# SubHarmonics_Main_Board_v2.net
KiCad netlist of a schematic drawn in EAGLE
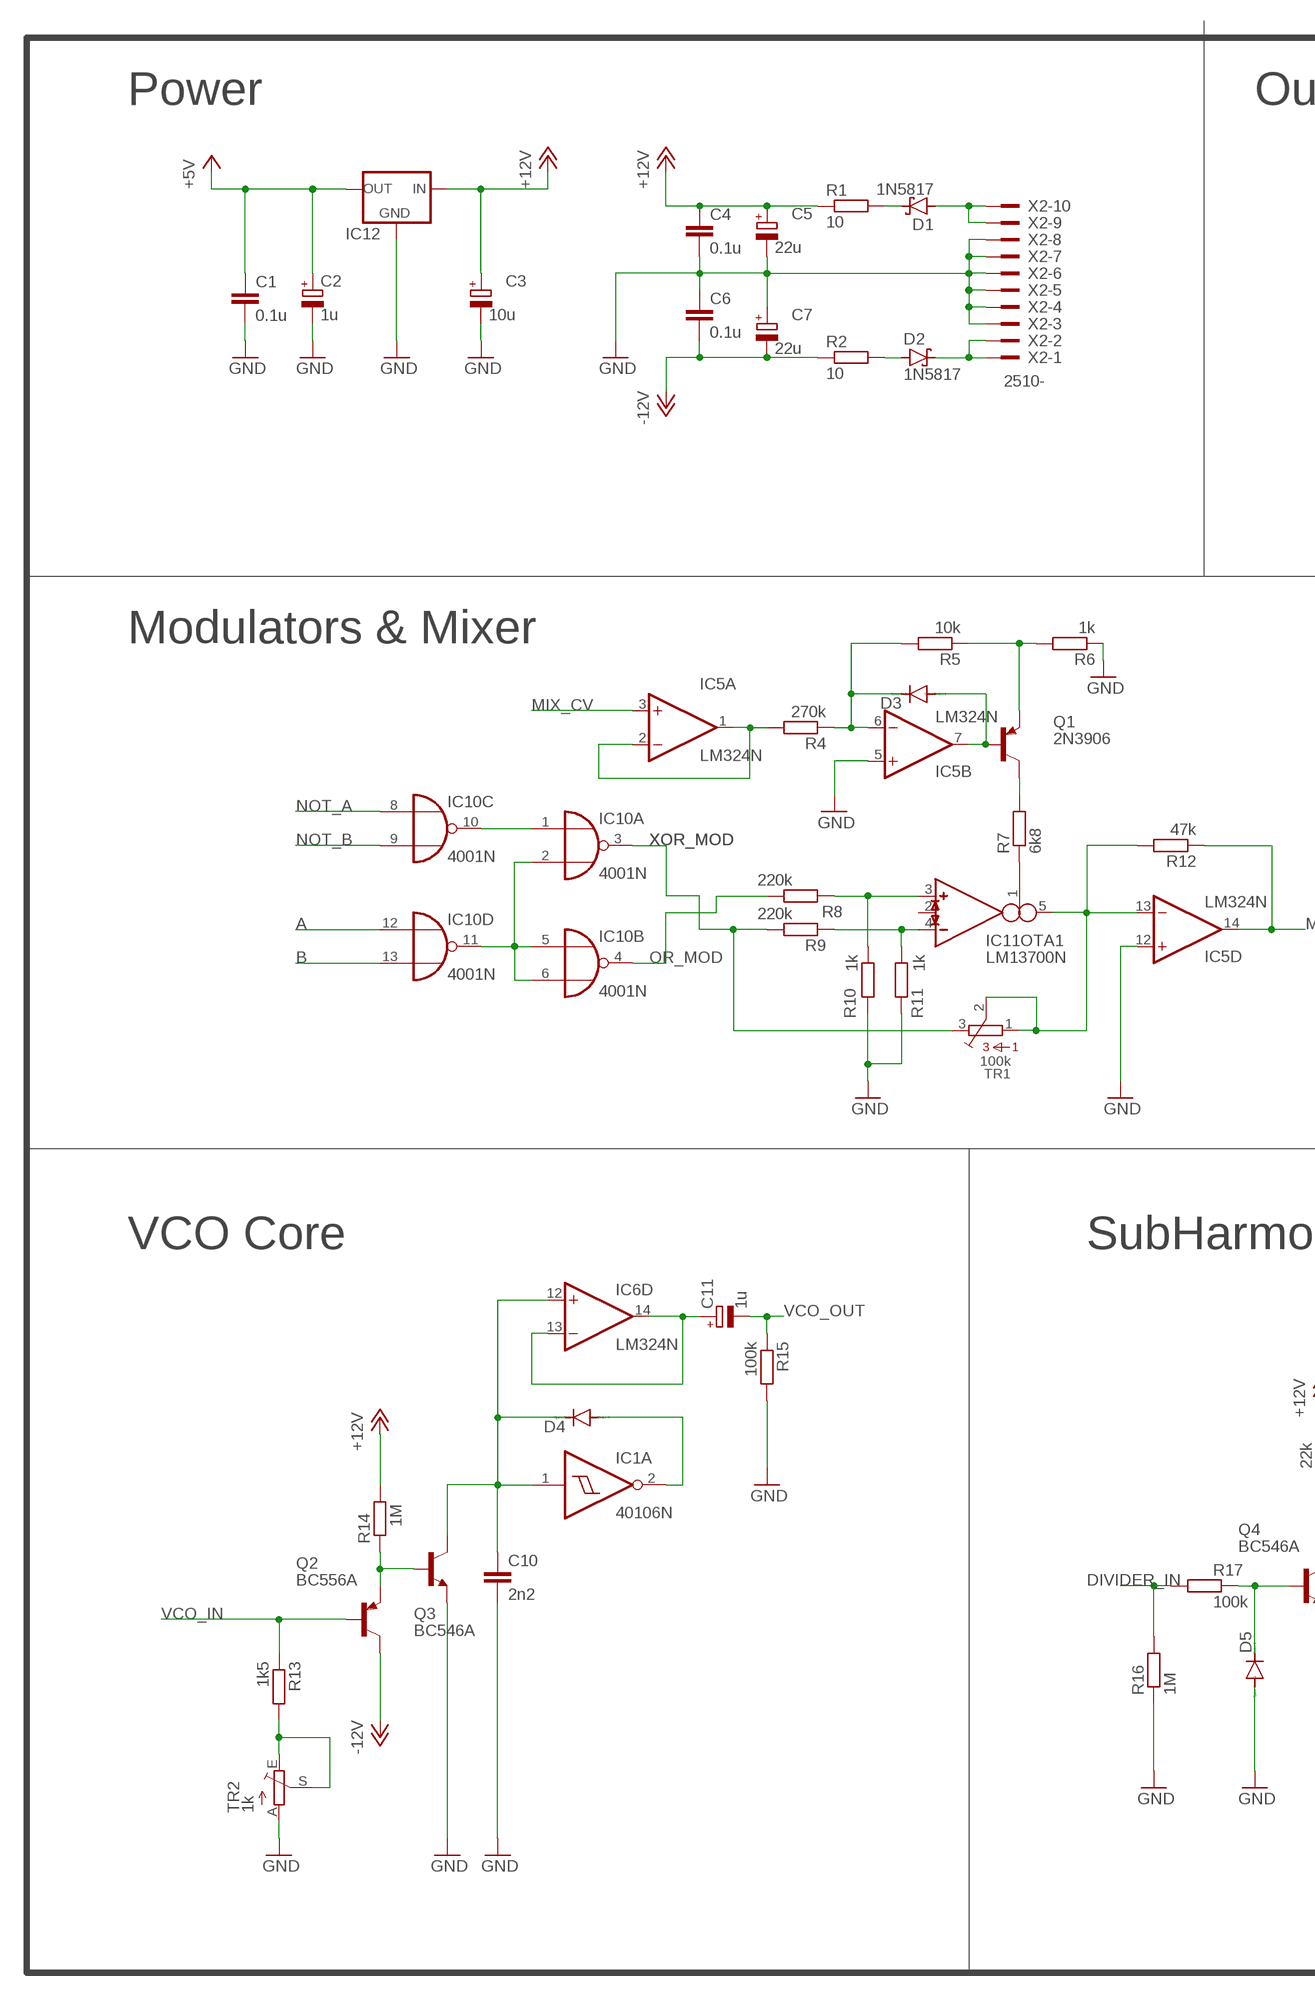
[diagram p0: schematic, sheet 1, part 1 of 2]
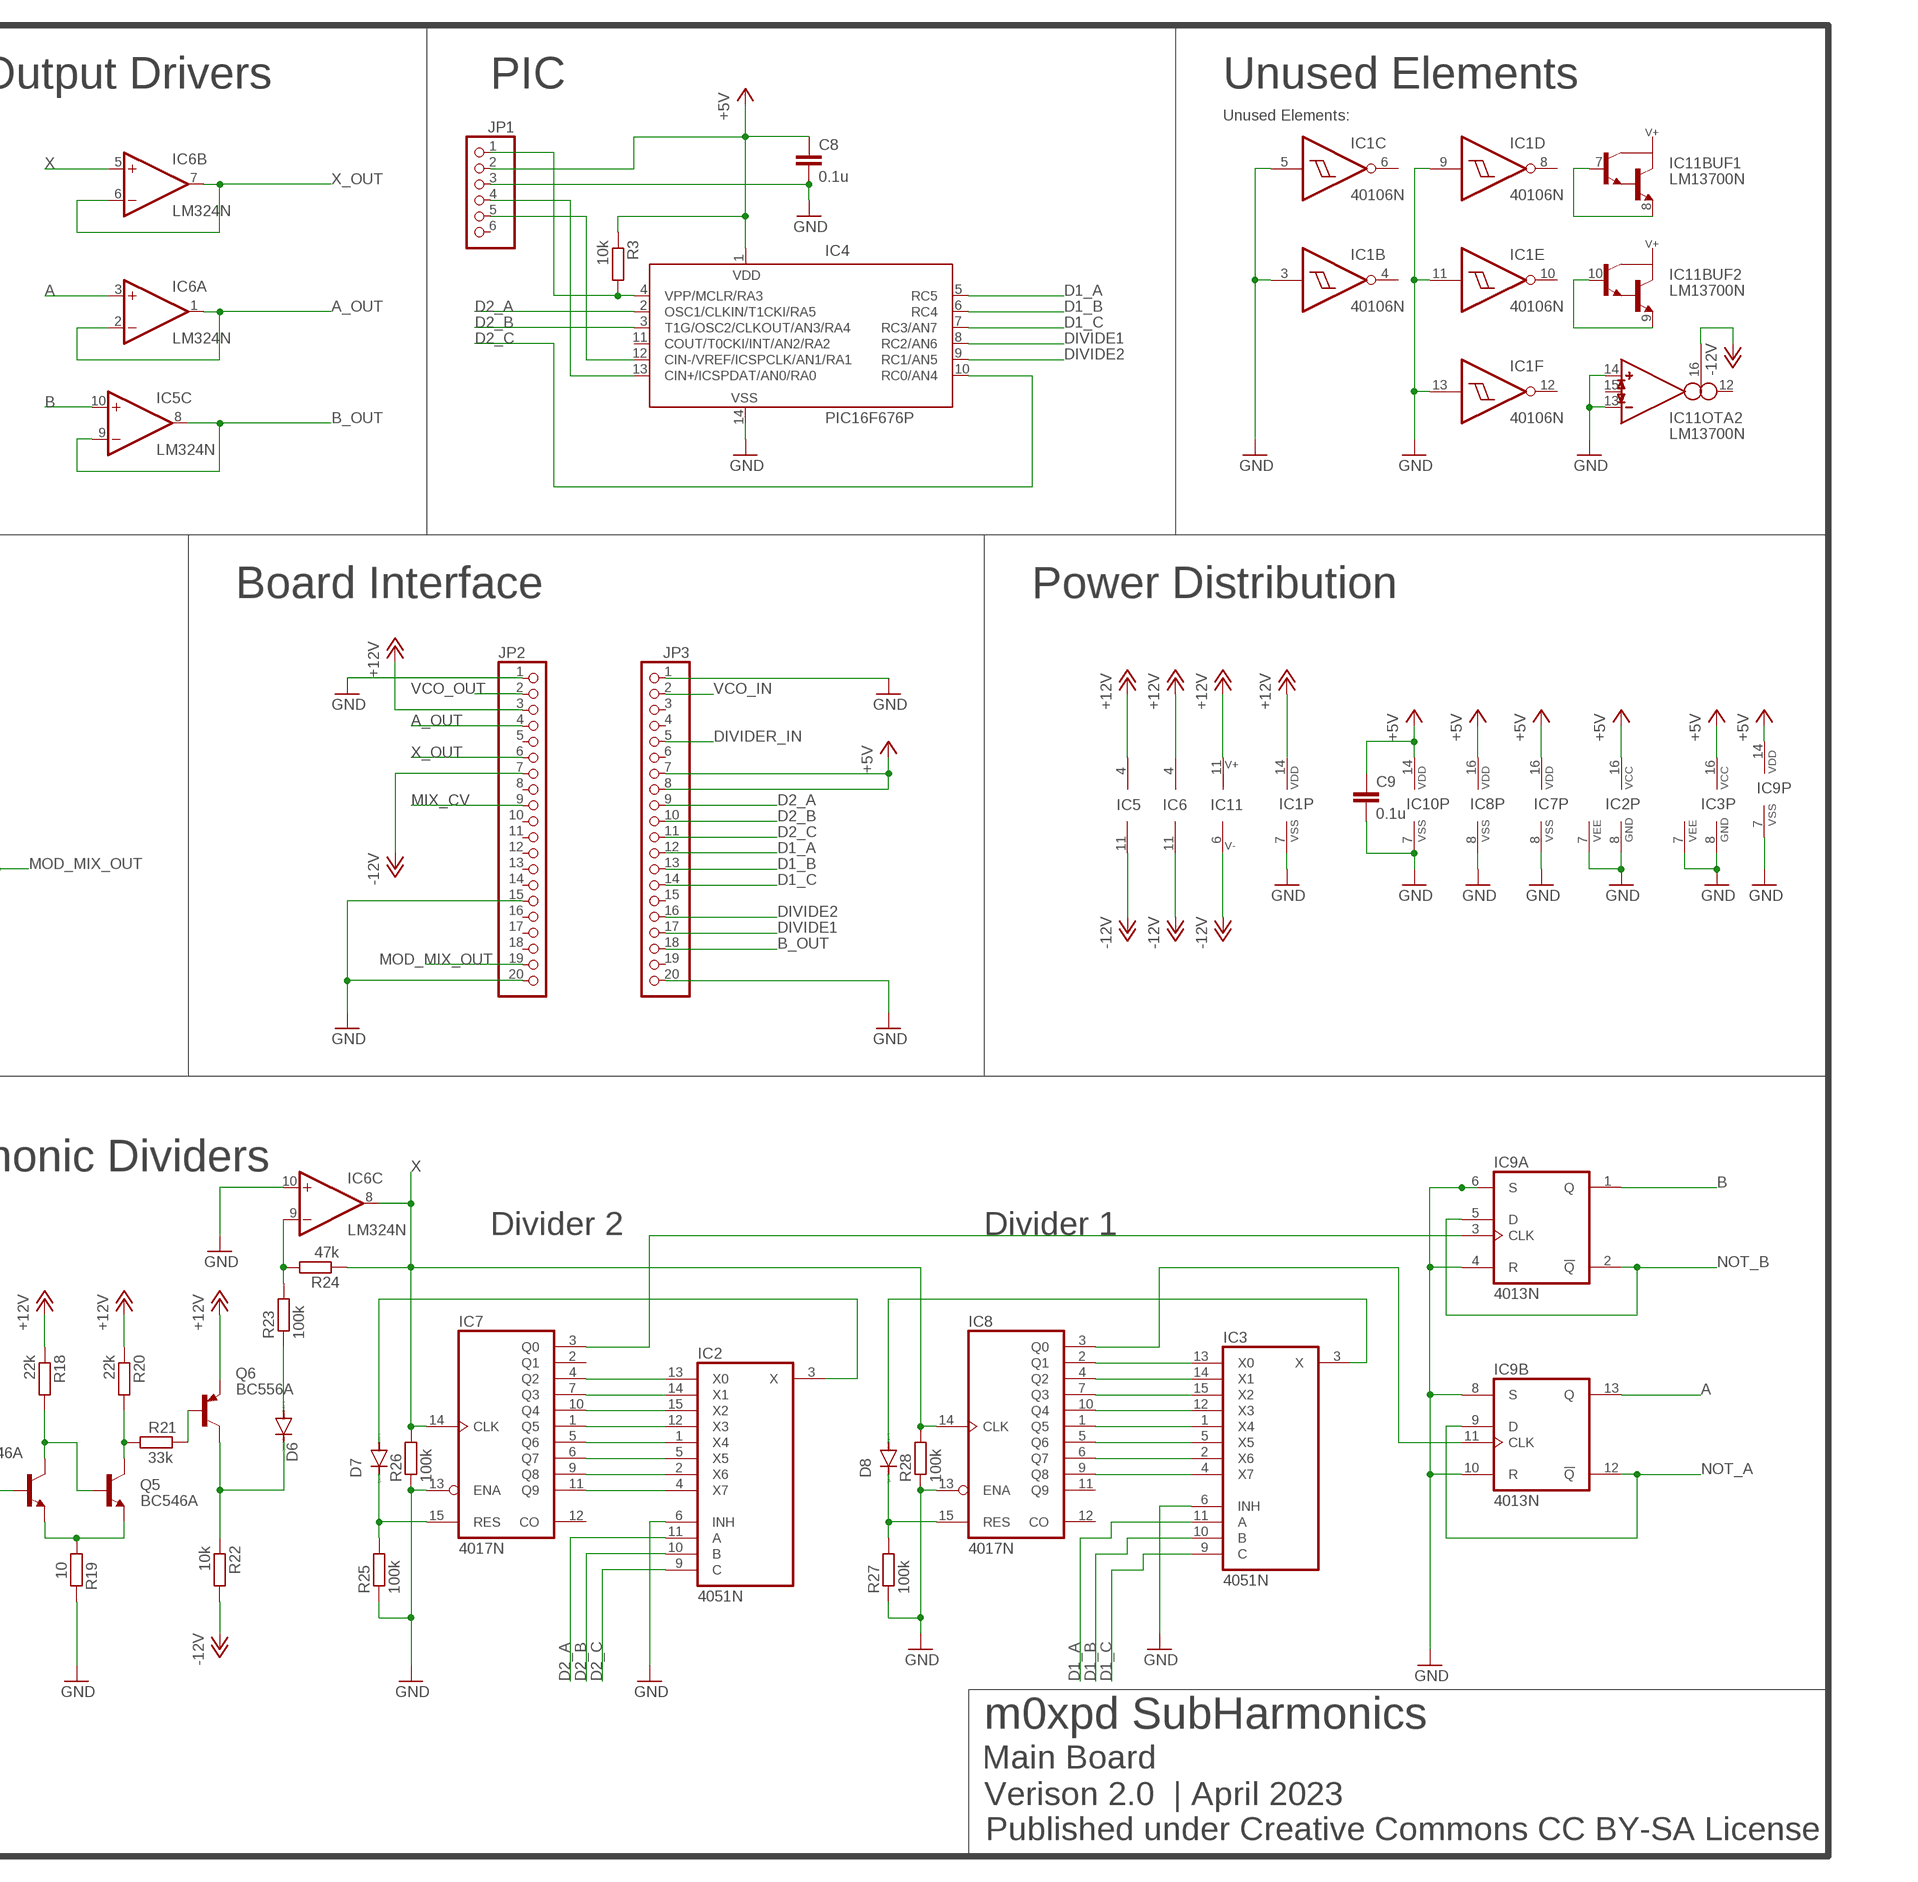
[diagram p1: schematic, sheet 1, part 2 of 2]

(export (version "E")
  (design (tool "Eeschema 10.0.6"))
  (components
    (comp (ref "C1")
      (value "0.1u")
      (footprint "eagle-import:C050-025X075")
      (libsource (lib "eagle-import") (part "C-EU050-025X075"))
    )
    (comp (ref "C2")
      (value "1u")
      (footprint "eagle-import:E2,5-5")
      (libsource (lib "eagle-import") (part "CPOL-EUE2.5-5"))
    )
    (comp (ref "C3")
      (value "10u")
      (footprint "eagle-import:E2,5-5")
      (libsource (lib "eagle-import") (part "CPOL-EUE2.5-5"))
    )
    (comp (ref "C4")
      (value "0.1u")
      (footprint "eagle-import:C050-025X075")
      (libsource (lib "eagle-import") (part "C-EU050-025X075"))
    )
    (comp (ref "C5")
      (value "22u")
      (footprint "eagle-import:E2,5-5")
      (libsource (lib "eagle-import") (part "CPOL-EUE2.5-5"))
    )
    (comp (ref "C6")
      (value "0.1u")
      (footprint "eagle-import:C050-025X075")
      (libsource (lib "eagle-import") (part "C-EU050-025X075"))
    )
    (comp (ref "C7")
      (value "22u")
      (footprint "eagle-import:E2,5-5")
      (libsource (lib "eagle-import") (part "CPOL-EUE2.5-5"))
    )
    (comp (ref "C8")
      (value "0.1u")
      (footprint "eagle-import:C050-025X075")
      (libsource (lib "eagle-import") (part "C-EU050-025X075"))
    )
    (comp (ref "C9")
      (value "0.1u")
      (footprint "eagle-import:C050-025X075")
      (libsource (lib "eagle-import") (part "C-EU050-025X075"))
    )
    (comp (ref "C10")
      (value "2n2")
      (footprint "eagle-import:C050-030X075")
      (libsource (lib "eagle-import") (part "C-EU050-030X075"))
    )
    (comp (ref "C11")
      (value "1u")
      (footprint "eagle-import:E2,5-5")
      (libsource (lib "eagle-import") (part "CPOL-EUE2.5-5"))
    )
    (comp (ref "D1")
      (value "1N5817")
      (footprint "eagle-import:DO35-7")
      (libsource (lib "eagle-import") (part "SCHOTTKY-DIODEDO35-7"))
    )
    (comp (ref "D2")
      (value "1N5817")
      (footprint "eagle-import:DO35-7")
      (libsource (lib "eagle-import") (part "SCHOTTKY-DIODEDO35-7"))
    )
    (comp (ref "D3")
      (value "1N4148DO35-7")
      (footprint "eagle-import:DO35-7")
      (libsource (lib "eagle-import") (part "1N4148DO35-7"))
    )
    (comp (ref "D4")
      (value "1N4148DO35-7")
      (footprint "eagle-import:DO35-7")
      (libsource (lib "eagle-import") (part "1N4148DO35-7"))
    )
    (comp (ref "D5")
      (value "1N4148DO35-7")
      (footprint "eagle-import:DO35-7")
      (libsource (lib "eagle-import") (part "1N4148DO35-7"))
    )
    (comp (ref "D6")
      (value "1N4148DO35-7")
      (footprint "eagle-import:DO35-7")
      (libsource (lib "eagle-import") (part "1N4148DO35-7"))
    )
    (comp (ref "D7")
      (value "1N4148DO35-7")
      (footprint "eagle-import:DO35-7")
      (libsource (lib "eagle-import") (part "1N4148DO35-7"))
    )
    (comp (ref "D8")
      (value "1N4148DO35-7")
      (footprint "eagle-import:DO35-7")
      (libsource (lib "eagle-import") (part "1N4148DO35-7"))
    )
    (comp (ref "IC1")
      (value "40106N")
      (footprint "eagle-import:DIL14")
      (libsource (lib "eagle-import") (part "40106N"))
    )
    (comp (ref "IC2")
      (value "4051N")
      (footprint "eagle-import:DIL16")
      (libsource (lib "eagle-import") (part "4051N"))
    )
    (comp (ref "IC3")
      (value "4051N")
      (footprint "eagle-import:DIL16")
      (libsource (lib "eagle-import") (part "4051N"))
    )
    (comp (ref "IC4")
      (value "PIC16F676P")
      (footprint "eagle-import:DIL14")
      (fields (field (name "MF") "MICROCHIP") (field (name "MPN") "PIC16F676-I/P"))
      (libsource (lib "eagle-import") (part "PIC16F676P"))
    )
    (comp (ref "IC5")
      (value "LM324N")
      (footprint "eagle-import:DIL14")
      (libsource (lib "eagle-import") (part "LM324N"))
    )
    (comp (ref "IC6")
      (value "LM324N")
      (footprint "eagle-import:DIL14")
      (libsource (lib "eagle-import") (part "LM324N"))
    )
    (comp (ref "IC7")
      (value "4017N")
      (footprint "eagle-import:DIL16")
      (libsource (lib "eagle-import") (part "4017N"))
    )
    (comp (ref "IC8")
      (value "4017N")
      (footprint "eagle-import:DIL16")
      (libsource (lib "eagle-import") (part "4017N"))
    )
    (comp (ref "IC9")
      (value "4013N")
      (footprint "eagle-import:DIL14")
      (libsource (lib "eagle-import") (part "4013N"))
    )
    (comp (ref "IC10")
      (value "4001N")
      (footprint "eagle-import:DIL14")
      (libsource (lib "eagle-import") (part "4001N"))
    )
    (comp (ref "IC11")
      (value "LM13700N")
      (footprint "eagle-import:DIL16")
      (libsource (lib "eagle-import") (part "LM13700N"))
    )
    (comp (ref "IC12")
      (value "78LXX")
      (footprint "eagle-import:78LXX")
      (libsource (lib "eagle-import") (part "78LXX"))
    )
    (comp (ref "JP1")
      (value "PINHD-1X6")
      (footprint "eagle-import:1X06")
      (libsource (lib "eagle-import") (part "PINHD-1X6"))
    )
    (comp (ref "JP2")
      (value "PINHD-1X20")
      (footprint "eagle-import:1X20")
      (libsource (lib "eagle-import") (part "PINHD-1X20"))
    )
    (comp (ref "JP3")
      (value "PINHD-1X20")
      (footprint "eagle-import:1X20")
      (libsource (lib "eagle-import") (part "PINHD-1X20"))
    )
    (comp (ref "Q1")
      (value "2N3906")
      (footprint "eagle-import:TO92")
      (libsource (lib "eagle-import") (part "2N3906"))
    )
    (comp (ref "Q2")
      (value "BC556A")
      (footprint "eagle-import:TO92-EBC")
      (libsource (lib "eagle-import") (part "BC556A"))
    )
    (comp (ref "Q3")
      (value "BC546A")
      (footprint "eagle-import:TO92-EBC")
      (libsource (lib "eagle-import") (part "BC546A"))
    )
    (comp (ref "Q4")
      (value "BC546A")
      (footprint "eagle-import:TO92-EBC")
      (libsource (lib "eagle-import") (part "BC546A"))
    )
    (comp (ref "Q5")
      (value "BC546A")
      (footprint "eagle-import:TO92-EBC")
      (libsource (lib "eagle-import") (part "BC546A"))
    )
    (comp (ref "Q6")
      (value "BC556A")
      (footprint "eagle-import:TO92-EBC")
      (libsource (lib "eagle-import") (part "BC556"))
    )
    (comp (ref "R1")
      (value "10")
      (footprint "eagle-import:0204_7")
      (libsource (lib "eagle-import") (part "R-EU_0204/7"))
    )
    (comp (ref "R2")
      (value "10")
      (footprint "eagle-import:0204_7")
      (libsource (lib "eagle-import") (part "R-EU_0204/7"))
    )
    (comp (ref "R3")
      (value "10k")
      (footprint "eagle-import:0204_7")
      (libsource (lib "eagle-import") (part "R-EU_0204/7"))
    )
    (comp (ref "R4")
      (value "270k")
      (footprint "eagle-import:0204_7")
      (libsource (lib "eagle-import") (part "R-EU_0204/7"))
    )
    (comp (ref "R5")
      (value "10k")
      (footprint "eagle-import:0204_7")
      (libsource (lib "eagle-import") (part "R-EU_0204/7"))
    )
    (comp (ref "R6")
      (value "1k")
      (footprint "eagle-import:0204_7")
      (libsource (lib "eagle-import") (part "R-EU_0204/7"))
    )
    (comp (ref "R7")
      (value "6k8")
      (footprint "eagle-import:0204_7")
      (libsource (lib "eagle-import") (part "R-EU_0204/7"))
    )
    (comp (ref "R8")
      (value "220k")
      (footprint "eagle-import:0204_7")
      (libsource (lib "eagle-import") (part "R-EU_0204/7"))
    )
    (comp (ref "R9")
      (value "220k")
      (footprint "eagle-import:0204_7")
      (libsource (lib "eagle-import") (part "R-EU_0204/7"))
    )
    (comp (ref "R10")
      (value "1k")
      (footprint "eagle-import:0204_7")
      (libsource (lib "eagle-import") (part "R-EU_0204/7"))
    )
    (comp (ref "R11")
      (value "1k")
      (footprint "eagle-import:0204_7")
      (libsource (lib "eagle-import") (part "R-EU_0204/7"))
    )
    (comp (ref "R12")
      (value "47k")
      (footprint "eagle-import:0204_7")
      (libsource (lib "eagle-import") (part "R-EU_0204/7"))
    )
    (comp (ref "R13")
      (value "1k5")
      (footprint "eagle-import:0204_7")
      (libsource (lib "eagle-import") (part "R-EU_0204/7"))
    )
    (comp (ref "R14")
      (value "1M")
      (footprint "eagle-import:0204_7")
      (libsource (lib "eagle-import") (part "R-EU_0204/7"))
    )
    (comp (ref "R15")
      (value "100k")
      (footprint "eagle-import:0204_7")
      (libsource (lib "eagle-import") (part "R-EU_0204/7"))
    )
    (comp (ref "R16")
      (value "1M")
      (footprint "eagle-import:0204_7")
      (libsource (lib "eagle-import") (part "R-EU_0204/7"))
    )
    (comp (ref "R17")
      (value "100k")
      (footprint "eagle-import:0204_7")
      (libsource (lib "eagle-import") (part "R-EU_0204/7"))
    )
    (comp (ref "R18")
      (value "22k")
      (footprint "eagle-import:0204_7")
      (libsource (lib "eagle-import") (part "R-EU_0204/7"))
    )
    (comp (ref "R19")
      (value "10")
      (footprint "eagle-import:0204_7")
      (libsource (lib "eagle-import") (part "R-EU_0204/7"))
    )
    (comp (ref "R20")
      (value "22k")
      (footprint "eagle-import:0204_7")
      (libsource (lib "eagle-import") (part "R-EU_0204/7"))
    )
    (comp (ref "R21")
      (value "33k")
      (footprint "eagle-import:0204_7")
      (libsource (lib "eagle-import") (part "R-EU_0204/7"))
    )
    (comp (ref "R22")
      (value "10k")
      (footprint "eagle-import:0204_7")
      (libsource (lib "eagle-import") (part "R-EU_0204/7"))
    )
    (comp (ref "R23")
      (value "100k")
      (footprint "eagle-import:0204_7")
      (libsource (lib "eagle-import") (part "R-EU_0204/7"))
    )
    (comp (ref "R24")
      (value "47k")
      (footprint "eagle-import:0204_7")
      (libsource (lib "eagle-import") (part "R-EU_0204/7"))
    )
    (comp (ref "R25")
      (value "100k")
      (footprint "eagle-import:0204_7")
      (libsource (lib "eagle-import") (part "R-EU_0204/7"))
    )
    (comp (ref "R26")
      (value "100k")
      (footprint "eagle-import:0204_7")
      (libsource (lib "eagle-import") (part "R-EU_0204/7"))
    )
    (comp (ref "R27")
      (value "100k")
      (footprint "eagle-import:0204_7")
      (libsource (lib "eagle-import") (part "R-EU_0204/7"))
    )
    (comp (ref "R28")
      (value "100k")
      (footprint "eagle-import:0204_7")
      (libsource (lib "eagle-import") (part "R-EU_0204/7"))
    )
    (comp (ref "TR1")
      (value "100k")
      (footprint "eagle-import:BOURNS_3362P_TRIMMER")
      (libsource (lib "eagle-import") (part "BOURNS_3362P_TRIMMERP"))
    )
    (comp (ref "TR2")
      (value "1k")
      (footprint "eagle-import:B64Y")
      (libsource (lib "eagle-import") (part "TRIM_EU-B64Y"))
    )
    (comp (ref "X2")
      (value "2510-")
      (footprint "eagle-import:PAK100_2500-10")
      (fields (field (name "MF") "3M") (field (name "MPN") "2510-6002UB"))
      (libsource (lib "eagle-import") (part "2510-"))
    )
  )
  (nets
    (net (code "1") (name "+5V") (class "Default")
      (node (ref "C1") (pin "1") (pinfunction "1_1") (pintype "passive"))
      (node (ref "C2") (pin "+") (pinfunction "+_+") (pintype "passive"))
      (node (ref "C8") (pin "1") (pinfunction "1_1") (pintype "passive"))
      (node (ref "C9") (pin "1") (pinfunction "1_1") (pintype "passive"))
      (node (ref "IC10") (pin "14") (pinfunction "VDD_14") (pintype "power_in"))
      (node (ref "IC12") (pin "OUT") (pinfunction "OUT_OUT") (pintype "passive"))
      (node (ref "IC2") (pin "16") (pinfunction "VCC_16") (pintype "power_in"))
      (node (ref "IC3") (pin "16") (pinfunction "VCC_16") (pintype "power_in"))
      (node (ref "IC4") (pin "1") (pinfunction "VDD_1") (pintype "power_in"))
      (node (ref "IC7") (pin "16") (pinfunction "VDD_16") (pintype "power_in"))
      (node (ref "IC8") (pin "16") (pinfunction "VDD_16") (pintype "power_in"))
      (node (ref "IC9") (pin "14") (pinfunction "VDD_14") (pintype "power_in"))
      (node (ref "JP1") (pin "2") (pinfunction "2_2") (pintype "passive"))
      (node (ref "JP3") (pin "7") (pinfunction "7_7") (pintype "passive"))
      (node (ref "JP3") (pin "8") (pinfunction "8_8") (pintype "passive"))
      (node (ref "R3") (pin "1") (pinfunction "1_1") (pintype "passive"))
    )
    (net (code "2") (name "+12V") (class "Default")
      (node (ref "C3") (pin "+") (pinfunction "+_+") (pintype "passive"))
      (node (ref "C4") (pin "1") (pinfunction "1_1") (pintype "passive"))
      (node (ref "C5") (pin "+") (pinfunction "+_+") (pintype "passive"))
      (node (ref "IC1") (pin "14") (pinfunction "VDD_14") (pintype "power_in"))
      (node (ref "IC11") (pin "11") (pinfunction "V+_11") (pintype "power_in"))
      (node (ref "IC12") (pin "IN") (pinfunction "IN_IN") (pintype "input"))
      (node (ref "IC5") (pin "4") (pinfunction "V+_4") (pintype "power_in"))
      (node (ref "IC6") (pin "4") (pinfunction "V+_4") (pintype "power_in"))
      (node (ref "JP2") (pin "3") (pinfunction "3_3") (pintype "passive"))
      (node (ref "Q6") (pin "E") (pinfunction "E_E") (pintype "passive"))
      (node (ref "R1") (pin "1") (pinfunction "1_1") (pintype "passive"))
      (node (ref "R14") (pin "2") (pinfunction "2_2") (pintype "passive"))
      (node (ref "R18") (pin "1") (pinfunction "1_1") (pintype "passive"))
      (node (ref "R20") (pin "1") (pinfunction "1_1") (pintype "passive"))
    )
    (net (code "3") (name "-12V") (class "Default")
      (node (ref "C6") (pin "2") (pinfunction "2_2") (pintype "passive"))
      (node (ref "C7") (pin "-") (pinfunction "-_-") (pintype "passive"))
      (node (ref "IC11") (pin "16") (pinfunction "I_BIAS_16") (pintype "input"))
      (node (ref "IC11") (pin "6") (pinfunction "V-_6") (pintype "power_in"))
      (node (ref "IC5") (pin "11") (pinfunction "V-_11") (pintype "power_in"))
      (node (ref "IC6") (pin "11") (pinfunction "V-_11") (pintype "power_in"))
      (node (ref "JP2") (pin "7") (pinfunction "7_7") (pintype "passive"))
      (node (ref "Q2") (pin "C") (pinfunction "C_C") (pintype "passive"))
      (node (ref "R2") (pin "1") (pinfunction "1_1") (pintype "passive"))
      (node (ref "R22") (pin "2") (pinfunction "2_2") (pintype "passive"))
    )
    (net (code "4") (name "/A") (class "Default")
      (node (ref "IC10") (pin "12") (pinfunction "I0_12") (pintype "input"))
      (node (ref "IC6") (pin "3") (pinfunction "+IN_3") (pintype "input"))
      (node (ref "IC9") (pin "13") (pinfunction "Q_13") (pintype "output"))
    )
    (net (code "5") (name "/A_OUT") (class "Default")
      (node (ref "IC6") (pin "1") (pinfunction "OUT_1") (pintype "output"))
      (node (ref "IC6") (pin "2") (pinfunction "-IN_2") (pintype "input"))
      (node (ref "JP2") (pin "4") (pinfunction "4_4") (pintype "passive"))
    )
    (net (code "6") (name "/B") (class "Default")
      (node (ref "IC10") (pin "13") (pinfunction "I1_13") (pintype "input"))
      (node (ref "IC5") (pin "10") (pinfunction "+IN_10") (pintype "input"))
      (node (ref "IC9") (pin "1") (pinfunction "Q_1") (pintype "output"))
    )
    (net (code "7") (name "/B_OUT") (class "Default")
      (node (ref "IC5") (pin "8") (pinfunction "OUT_8") (pintype "output"))
      (node (ref "IC5") (pin "9") (pinfunction "-IN_9") (pintype "input"))
      (node (ref "JP3") (pin "18") (pinfunction "18_18") (pintype "passive"))
    )
    (net (code "8") (name "/D1_A") (class "Default")
      (node (ref "IC3") (pin "11") (pinfunction "A_11") (pintype "input"))
      (node (ref "IC4") (pin "5") (pinfunction "RC5_5") (pintype "bidirectional"))
      (node (ref "JP3") (pin "12") (pinfunction "12_12") (pintype "passive"))
    )
    (net (code "9") (name "/D1_B") (class "Default")
      (node (ref "IC3") (pin "10") (pinfunction "B_10") (pintype "input"))
      (node (ref "IC4") (pin "6") (pinfunction "RC4_6") (pintype "bidirectional"))
      (node (ref "JP3") (pin "13") (pinfunction "13_13") (pintype "passive"))
    )
    (net (code "10") (name "/D1_C") (class "Default")
      (node (ref "IC3") (pin "9") (pinfunction "C_9") (pintype "input"))
      (node (ref "IC4") (pin "7") (pinfunction "RC3/AN7_7") (pintype "bidirectional"))
      (node (ref "JP3") (pin "14") (pinfunction "14_14") (pintype "passive"))
    )
    (net (code "11") (name "/D2_A") (class "Default")
      (node (ref "IC2") (pin "11") (pinfunction "A_11") (pintype "input"))
      (node (ref "IC4") (pin "2") (pinfunction "OSC1/CLKIN/T1CKI/RA5_2") (pintype "bidirectional"))
      (node (ref "JP3") (pin "9") (pinfunction "9_9") (pintype "passive"))
    )
    (net (code "12") (name "/D2_B") (class "Default")
      (node (ref "IC2") (pin "10") (pinfunction "B_10") (pintype "input"))
      (node (ref "IC4") (pin "3") (pinfunction "T1G/OSC2/CLKOUT/AN3/RA4_3") (pintype "bidirectional"))
      (node (ref "JP3") (pin "10") (pinfunction "10_10") (pintype "passive"))
    )
    (net (code "13") (name "/D2_C") (class "Default")
      (node (ref "IC2") (pin "9") (pinfunction "C_9") (pintype "input"))
      (node (ref "IC4") (pin "10") (pinfunction "RC0/AN4_10") (pintype "bidirectional"))
      (node (ref "JP3") (pin "11") (pinfunction "11_11") (pintype "passive"))
    )
    (net (code "14") (name "/DIVIDE1") (class "Default")
      (node (ref "IC4") (pin "8") (pinfunction "RC2/AN6_8") (pintype "bidirectional"))
      (node (ref "JP3") (pin "17") (pinfunction "17_17") (pintype "passive"))
    )
    (net (code "15") (name "/DIVIDE2") (class "Default")
      (node (ref "IC4") (pin "9") (pinfunction "RC1/AN5_9") (pintype "bidirectional"))
      (node (ref "JP3") (pin "16") (pinfunction "16_16") (pintype "passive"))
    )
    (net (code "16") (name "/DIVIDER_IN") (class "Default")
      (node (ref "JP3") (pin "5") (pinfunction "5_5") (pintype "passive"))
      (node (ref "R16") (pin "2") (pinfunction "2_2") (pintype "passive"))
      (node (ref "R17") (pin "1") (pinfunction "1_1") (pintype "passive"))
    )
    (net (code "17") (name "/MIX_CV") (class "Default")
      (node (ref "IC5") (pin "3") (pinfunction "+IN_3") (pintype "input"))
      (node (ref "JP2") (pin "9") (pinfunction "9_9") (pintype "passive"))
    )
    (net (code "18") (name "/MOD_MIX_OUT") (class "Default")
      (node (ref "IC5") (pin "14") (pinfunction "OUT_14") (pintype "output"))
      (node (ref "JP2") (pin "19") (pinfunction "19_19") (pintype "passive"))
      (node (ref "R12") (pin "1") (pinfunction "1_1") (pintype "passive"))
    )
    (net (code "19") (name "/NOT_A") (class "Default")
      (node (ref "IC10") (pin "8") (pinfunction "I0_8") (pintype "input"))
      (node (ref "IC9") (pin "12") (pinfunction "~{Q}_12") (pintype "output"))
      (node (ref "IC9") (pin "9") (pinfunction "D_9") (pintype "input"))
    )
    (net (code "20") (name "/NOT_B") (class "Default")
      (node (ref "IC10") (pin "9") (pinfunction "I1_9") (pintype "input"))
      (node (ref "IC9") (pin "2") (pinfunction "~{Q}_2") (pintype "output"))
      (node (ref "IC9") (pin "5") (pinfunction "D_5") (pintype "input"))
    )
    (net (code "21") (name "/OR_MOD") (class "Default")
      (node (ref "IC10") (pin "4") (pinfunction "O_4") (pintype "output"))
      (node (ref "R8") (pin "2") (pinfunction "2_2") (pintype "passive"))
    )
    (net (code "22") (name "/VCO_IN") (class "Default")
      (node (ref "JP3") (pin "2") (pinfunction "2_2") (pintype "passive"))
      (node (ref "Q2") (pin "B") (pinfunction "B_B") (pintype "passive"))
      (node (ref "R13") (pin "1") (pinfunction "1_1") (pintype "passive"))
    )
    (net (code "23") (name "/VCO_OUT") (class "Default")
      (node (ref "C11") (pin "-") (pinfunction "-_-") (pintype "passive"))
      (node (ref "JP2") (pin "2") (pinfunction "2_2") (pintype "passive"))
      (node (ref "R15") (pin "1") (pinfunction "1_1") (pintype "passive"))
    )
    (net (code "24") (name "/X") (class "Default")
      (node (ref "IC6") (pin "5") (pinfunction "+IN_5") (pintype "input"))
      (node (ref "IC6") (pin "8") (pinfunction "OUT_8") (pintype "output"))
      (node (ref "IC7") (pin "14") (pinfunction "CLK_14") (pintype "input"))
      (node (ref "IC8") (pin "14") (pinfunction "CLK_14") (pintype "input"))
      (node (ref "R24") (pin "1") (pinfunction "1_1") (pintype "passive"))
      (node (ref "R26") (pin "2") (pinfunction "2_2") (pintype "passive"))
      (node (ref "R28") (pin "2") (pinfunction "2_2") (pintype "passive"))
    )
    (net (code "25") (name "/XOR_MOD") (class "Default")
      (node (ref "IC10") (pin "3") (pinfunction "O_3") (pintype "output"))
      (node (ref "R9") (pin "2") (pinfunction "2_2") (pintype "passive"))
      (node (ref "TR1") (pin "3") (pinfunction "3_3") (pintype "passive"))
    )
    (net (code "26") (name "/X_OUT") (class "Default")
      (node (ref "IC6") (pin "6") (pinfunction "-IN_6") (pintype "input"))
      (node (ref "IC6") (pin "7") (pinfunction "OUT_7") (pintype "output"))
      (node (ref "JP2") (pin "6") (pinfunction "6_6") (pintype "passive"))
    )
    (net (code "27") (name "GND") (class "Default")
      (node (ref "C1") (pin "2") (pinfunction "2_2") (pintype "passive"))
      (node (ref "C10") (pin "2") (pinfunction "2_2") (pintype "passive"))
      (node (ref "C2") (pin "-") (pinfunction "-_-") (pintype "passive"))
      (node (ref "C3") (pin "-") (pinfunction "-_-") (pintype "passive"))
      (node (ref "C4") (pin "2") (pinfunction "2_2") (pintype "passive"))
      (node (ref "C5") (pin "-") (pinfunction "-_-") (pintype "passive"))
      (node (ref "C6") (pin "1") (pinfunction "1_1") (pintype "passive"))
      (node (ref "C7") (pin "+") (pinfunction "+_+") (pintype "passive"))
      (node (ref "C8") (pin "2") (pinfunction "2_2") (pintype "passive"))
      (node (ref "C9") (pin "2") (pinfunction "2_2") (pintype "passive"))
      (node (ref "D5") (pin "A") (pinfunction "A_A") (pintype "passive"))
      (node (ref "IC1") (pin "11") (pinfunction "I_11") (pintype "input"))
      (node (ref "IC1") (pin "13") (pinfunction "I_13") (pintype "input"))
      (node (ref "IC1") (pin "3") (pinfunction "I_3") (pintype "input"))
      (node (ref "IC1") (pin "5") (pinfunction "I_5") (pintype "input"))
      (node (ref "IC1") (pin "7") (pinfunction "VSS_7") (pintype "power_in"))
      (node (ref "IC1") (pin "9") (pinfunction "I_9") (pintype "input"))
      (node (ref "IC10") (pin "7") (pinfunction "VSS_7") (pintype "power_in"))
      (node (ref "IC11") (pin "13") (pinfunction "IN_N_13") (pintype "input"))
      (node (ref "IC11") (pin "14") (pinfunction "IN_P_14") (pintype "input"))
      (node (ref "IC12") (pin "GND") (pinfunction "GND_GND") (pintype "input"))
      (node (ref "IC2") (pin "6") (pinfunction "INH_6") (pintype "input"))
      (node (ref "IC2") (pin "7") (pinfunction "VEE_7") (pintype "power_in"))
      (node (ref "IC2") (pin "8") (pinfunction "GND_8") (pintype "power_in"))
      (node (ref "IC3") (pin "6") (pinfunction "INH_6") (pintype "input"))
      (node (ref "IC3") (pin "7") (pinfunction "VEE_7") (pintype "power_in"))
      (node (ref "IC3") (pin "8") (pinfunction "GND_8") (pintype "power_in"))
      (node (ref "IC4") (pin "14") (pinfunction "VSS_14") (pintype "power_in"))
      (node (ref "IC5") (pin "12") (pinfunction "+IN_12") (pintype "input"))
      (node (ref "IC5") (pin "5") (pinfunction "+IN_5") (pintype "input"))
      (node (ref "IC6") (pin "10") (pinfunction "+IN_10") (pintype "input"))
      (node (ref "IC7") (pin "13") (pinfunction "ENA_13") (pintype "input"))
      (node (ref "IC7") (pin "8") (pinfunction "VSS_8") (pintype "power_in"))
      (node (ref "IC8") (pin "13") (pinfunction "ENA_13") (pintype "input"))
      (node (ref "IC8") (pin "8") (pinfunction "VSS_8") (pintype "power_in"))
      (node (ref "IC9") (pin "10") (pinfunction "R_10") (pintype "input"))
      (node (ref "IC9") (pin "4") (pinfunction "R_4") (pintype "input"))
      (node (ref "IC9") (pin "6") (pinfunction "S_6") (pintype "input"))
      (node (ref "IC9") (pin "7") (pinfunction "VSS_7") (pintype "power_in"))
      (node (ref "IC9") (pin "8") (pinfunction "S_8") (pintype "input"))
      (node (ref "JP1") (pin "3") (pinfunction "3_3") (pintype "passive"))
      (node (ref "JP2") (pin "1") (pinfunction "1_1") (pintype "passive"))
      (node (ref "JP2") (pin "15") (pinfunction "15_15") (pintype "passive"))
      (node (ref "JP2") (pin "20") (pinfunction "20_20") (pintype "passive"))
      (node (ref "JP3") (pin "1") (pinfunction "1_1") (pintype "passive"))
      (node (ref "JP3") (pin "20") (pinfunction "20_20") (pintype "passive"))
      (node (ref "Q3") (pin "E") (pinfunction "E_E") (pintype "passive"))
      (node (ref "R10") (pin "2") (pinfunction "2_2") (pintype "passive"))
      (node (ref "R11") (pin "2") (pinfunction "2_2") (pintype "passive"))
      (node (ref "R15") (pin "2") (pinfunction "2_2") (pintype "passive"))
      (node (ref "R16") (pin "1") (pinfunction "1_1") (pintype "passive"))
      (node (ref "R19") (pin "2") (pinfunction "2_2") (pintype "passive"))
      (node (ref "R25") (pin "1") (pinfunction "1_1") (pintype "passive"))
      (node (ref "R26") (pin "1") (pinfunction "1_1") (pintype "passive"))
      (node (ref "R27") (pin "1") (pinfunction "1_1") (pintype "passive"))
      (node (ref "R28") (pin "1") (pinfunction "1_1") (pintype "passive"))
      (node (ref "R6") (pin "1") (pinfunction "1_1") (pintype "passive"))
      (node (ref "TR2") (pin "A") (pinfunction "A_A") (pintype "passive"))
      (node (ref "X2") (pin "3") (pinfunction "KL_3") (pintype "passive"))
      (node (ref "X2") (pin "4") (pinfunction "KL_4") (pintype "passive"))
      (node (ref "X2") (pin "5") (pinfunction "KL_5") (pintype "passive"))
      (node (ref "X2") (pin "6") (pinfunction "KL_6") (pintype "passive"))
      (node (ref "X2") (pin "7") (pinfunction "KL_7") (pintype "passive"))
      (node (ref "X2") (pin "8") (pinfunction "KL_8") (pintype "passive"))
    )
    (net (code "28") (name "Net-(D1-PadC)") (class "Default")
      (node (ref "D1") (pin "C") (pinfunction "C_C") (pintype "passive"))
      (node (ref "R1") (pin "2") (pinfunction "2_2") (pintype "passive"))
    )
    (net (code "29") (name "Net-(D2-PadA)") (class "Default")
      (node (ref "D2") (pin "A") (pinfunction "A_A") (pintype "passive"))
      (node (ref "R2") (pin "2") (pinfunction "2_2") (pintype "passive"))
    )
    (net (code "30") (name "Net-(D5-PadC)") (class "Default")
      (node (ref "D5") (pin "C") (pinfunction "C_C") (pintype "passive"))
      (node (ref "Q4") (pin "B") (pinfunction "B_B") (pintype "passive"))
      (node (ref "R17") (pin "2") (pinfunction "2_2") (pintype "passive"))
    )
    (net (code "31") (name "Net-(D6-PadA)") (class "Default")
      (node (ref "D6") (pin "A") (pinfunction "A_A") (pintype "passive"))
      (node (ref "R23") (pin "1") (pinfunction "1_1") (pintype "passive"))
    )
    (net (code "32") (name "Net-(D6-PadC)") (class "Default")
      (node (ref "D6") (pin "C") (pinfunction "C_C") (pintype "passive"))
      (node (ref "Q6") (pin "C") (pinfunction "C_C") (pintype "passive"))
      (node (ref "R22") (pin "1") (pinfunction "1_1") (pintype "passive"))
    )
    (net (code "33") (name "Net-(IC1A-I)") (class "Default")
      (node (ref "C10") (pin "1") (pinfunction "1_1") (pintype "passive"))
      (node (ref "D4") (pin "C") (pinfunction "C_C") (pintype "passive"))
      (node (ref "IC1") (pin "1") (pinfunction "I_1") (pintype "input"))
      (node (ref "IC6") (pin "12") (pinfunction "+IN_12") (pintype "input"))
      (node (ref "Q3") (pin "C") (pinfunction "C_C") (pintype "passive"))
    )
    (net (code "34") (name "Net-(IC1A-O)") (class "Default")
      (node (ref "D4") (pin "A") (pinfunction "A_A") (pintype "passive"))
      (node (ref "IC1") (pin "2") (pinfunction "O_2") (pintype "output"))
    )
    (net (code "35") (name "Net-(IC2A-X)") (class "Default")
      (node (ref "D7") (pin "A") (pinfunction "A_A") (pintype "passive"))
      (node (ref "IC2") (pin "3") (pinfunction "X_3") (pintype "bidirectional"))
    )
    (net (code "36") (name "Net-(IC2A-X0)") (class "Default")
      (node (ref "IC2") (pin "13") (pinfunction "X0_13") (pintype "bidirectional"))
      (node (ref "IC7") (pin "4") (pinfunction "Q2_4") (pintype "output"))
    )
    (net (code "37") (name "Net-(IC2A-X1)") (class "Default")
      (node (ref "IC2") (pin "14") (pinfunction "X1_14") (pintype "bidirectional"))
      (node (ref "IC7") (pin "7") (pinfunction "Q3_7") (pintype "output"))
    )
    (net (code "38") (name "Net-(IC2A-X2)") (class "Default")
      (node (ref "IC2") (pin "15") (pinfunction "X2_15") (pintype "bidirectional"))
      (node (ref "IC7") (pin "10") (pinfunction "Q4_10") (pintype "output"))
    )
    (net (code "39") (name "Net-(IC2A-X3)") (class "Default")
      (node (ref "IC2") (pin "12") (pinfunction "X3_12") (pintype "bidirectional"))
      (node (ref "IC7") (pin "1") (pinfunction "Q5_1") (pintype "output"))
    )
    (net (code "40") (name "Net-(IC2A-X4)") (class "Default")
      (node (ref "IC2") (pin "1") (pinfunction "X4_1") (pintype "bidirectional"))
      (node (ref "IC7") (pin "5") (pinfunction "Q6_5") (pintype "output"))
    )
    (net (code "41") (name "Net-(IC2A-X5)") (class "Default")
      (node (ref "IC2") (pin "5") (pinfunction "X5_5") (pintype "bidirectional"))
      (node (ref "IC7") (pin "6") (pinfunction "Q7_6") (pintype "output"))
    )
    (net (code "42") (name "Net-(IC2A-X6)") (class "Default")
      (node (ref "IC2") (pin "2") (pinfunction "X6_2") (pintype "bidirectional"))
      (node (ref "IC7") (pin "9") (pinfunction "Q8_9") (pintype "output"))
    )
    (net (code "43") (name "Net-(IC2A-X7)") (class "Default")
      (node (ref "IC2") (pin "4") (pinfunction "X7_4") (pintype "bidirectional"))
      (node (ref "IC7") (pin "11") (pinfunction "Q9_11") (pintype "output"))
    )
    (net (code "44") (name "Net-(IC3A-X)") (class "Default")
      (node (ref "D8") (pin "A") (pinfunction "A_A") (pintype "passive"))
      (node (ref "IC3") (pin "3") (pinfunction "X_3") (pintype "bidirectional"))
    )
    (net (code "45") (name "Net-(IC3A-X0)") (class "Default")
      (node (ref "IC3") (pin "13") (pinfunction "X0_13") (pintype "bidirectional"))
      (node (ref "IC8") (pin "2") (pinfunction "Q1_2") (pintype "output"))
    )
    (net (code "46") (name "Net-(IC3A-X1)") (class "Default")
      (node (ref "IC3") (pin "14") (pinfunction "X1_14") (pintype "bidirectional"))
      (node (ref "IC8") (pin "4") (pinfunction "Q2_4") (pintype "output"))
    )
    (net (code "47") (name "Net-(IC3A-X2)") (class "Default")
      (node (ref "IC3") (pin "15") (pinfunction "X2_15") (pintype "bidirectional"))
      (node (ref "IC8") (pin "7") (pinfunction "Q3_7") (pintype "output"))
    )
    (net (code "48") (name "Net-(IC3A-X3)") (class "Default")
      (node (ref "IC3") (pin "12") (pinfunction "X3_12") (pintype "bidirectional"))
      (node (ref "IC8") (pin "10") (pinfunction "Q4_10") (pintype "output"))
    )
    (net (code "49") (name "Net-(IC3A-X4)") (class "Default")
      (node (ref "IC3") (pin "1") (pinfunction "X4_1") (pintype "bidirectional"))
      (node (ref "IC8") (pin "1") (pinfunction "Q5_1") (pintype "output"))
    )
    (net (code "50") (name "Net-(IC3A-X5)") (class "Default")
      (node (ref "IC3") (pin "5") (pinfunction "X5_5") (pintype "bidirectional"))
      (node (ref "IC8") (pin "5") (pinfunction "Q6_5") (pintype "output"))
    )
    (net (code "51") (name "Net-(IC3A-X6)") (class "Default")
      (node (ref "IC3") (pin "2") (pinfunction "X6_2") (pintype "bidirectional"))
      (node (ref "IC8") (pin "6") (pinfunction "Q7_6") (pintype "output"))
    )
    (net (code "52") (name "Net-(IC3A-X7)") (class "Default")
      (node (ref "IC3") (pin "4") (pinfunction "X7_4") (pintype "bidirectional"))
      (node (ref "IC8") (pin "9") (pinfunction "Q8_9") (pintype "output"))
    )
    (net (code "53") (name "Net-(IC4-CIN+{slash}ICSPDAT{slash}AN0{slash}RA0)") (class "Default")
      (node (ref "IC4") (pin "13") (pinfunction "CIN+/ICSPDAT/AN0/RA0_13") (pintype "bidirectional"))
      (node (ref "JP1") (pin "4") (pinfunction "4_4") (pintype "passive"))
    )
    (net (code "54") (name "Net-(IC4-CIN-{slash}VREF{slash}ICSPCLK{slash}AN1{slash}RA1)") (class "Default")
      (node (ref "IC4") (pin "12") (pinfunction "CIN-/VREF/ICSPCLK/AN1/RA1_12") (pintype "bidirectional"))
      (node (ref "JP1") (pin "5") (pinfunction "5_5") (pintype "passive"))
    )
    (net (code "55") (name "Net-(IC4-VPP{slash}MCLR{slash}RA3)") (class "Default")
      (node (ref "IC4") (pin "4") (pinfunction "VPP/MCLR/RA3_4") (pintype "input"))
      (node (ref "JP1") (pin "1") (pinfunction "1_1") (pintype "passive"))
      (node (ref "R3") (pin "2") (pinfunction "2_2") (pintype "passive"))
    )
    (net (code "56") (name "Net-(IC5A--IN)") (class "Default")
      (node (ref "IC5") (pin "1") (pinfunction "OUT_1") (pintype "output"))
      (node (ref "IC5") (pin "2") (pinfunction "-IN_2") (pintype "input"))
      (node (ref "R4") (pin "2") (pinfunction "2_2") (pintype "passive"))
    )
    (net (code "57") (name "Net-(IC5B--IN)") (class "Default")
      (node (ref "D3") (pin "C") (pinfunction "C_C") (pintype "passive"))
      (node (ref "IC5") (pin "6") (pinfunction "-IN_6") (pintype "input"))
      (node (ref "R4") (pin "1") (pinfunction "1_1") (pintype "passive"))
      (node (ref "R5") (pin "2") (pinfunction "2_2") (pintype "passive"))
    )
    (net (code "58") (name "Net-(IC5B-OUT)") (class "Default")
      (node (ref "D3") (pin "A") (pinfunction "A_A") (pintype "passive"))
      (node (ref "IC5") (pin "7") (pinfunction "OUT_7") (pintype "output"))
      (node (ref "Q1") (pin "2") (pinfunction "B_2") (pintype "passive"))
    )
    (net (code "59") (name "Net-(IC6C--IN)") (class "Default")
      (node (ref "IC6") (pin "9") (pinfunction "-IN_9") (pintype "input"))
      (node (ref "R23") (pin "2") (pinfunction "2_2") (pintype "passive"))
      (node (ref "R24") (pin "2") (pinfunction "2_2") (pintype "passive"))
    )
    (net (code "60") (name "Net-(IC6D--IN)") (class "Default")
      (node (ref "C11") (pin "+") (pinfunction "+_+") (pintype "passive"))
      (node (ref "IC6") (pin "13") (pinfunction "-IN_13") (pintype "input"))
      (node (ref "IC6") (pin "14") (pinfunction "OUT_14") (pintype "output"))
    )
    (net (code "61") (name "Net-(IC7A-Q0)") (class "Default")
      (node (ref "IC7") (pin "3") (pinfunction "Q0_3") (pintype "output"))
      (node (ref "IC9") (pin "3") (pinfunction "CLK_3") (pintype "input"))
    )
    (net (code "62") (name "Net-(IC7A-RES)") (class "Default")
      (node (ref "D7") (pin "C") (pinfunction "C_C") (pintype "passive"))
      (node (ref "IC7") (pin "15") (pinfunction "RES_15") (pintype "input"))
      (node (ref "R25") (pin "2") (pinfunction "2_2") (pintype "passive"))
    )
    (net (code "63") (name "Net-(IC8A-Q0)") (class "Default")
      (node (ref "IC8") (pin "3") (pinfunction "Q0_3") (pintype "output"))
      (node (ref "IC9") (pin "11") (pinfunction "CLK_11") (pintype "input"))
    )
    (net (code "64") (name "Net-(IC8A-RES)") (class "Default")
      (node (ref "D8") (pin "C") (pinfunction "C_C") (pintype "passive"))
      (node (ref "IC8") (pin "15") (pinfunction "RES_15") (pintype "input"))
      (node (ref "R27") (pin "2") (pinfunction "2_2") (pintype "passive"))
    )
    (net (code "65") (name "Net-(IC10A-I0)") (class "Default")
      (node (ref "IC10") (pin "1") (pinfunction "I0_1") (pintype "input"))
      (node (ref "IC10") (pin "10") (pinfunction "O_10") (pintype "output"))
    )
    (net (code "66") (name "Net-(IC10A-I1)") (class "Default")
      (node (ref "IC10") (pin "11") (pinfunction "O_11") (pintype "output"))
      (node (ref "IC10") (pin "2") (pinfunction "I1_2") (pintype "input"))
      (node (ref "IC10") (pin "5") (pinfunction "I0_5") (pintype "input"))
      (node (ref "IC10") (pin "6") (pinfunction "I1_6") (pintype "input"))
    )
    (net (code "67") (name "Net-(IC11A-B)") (class "Default")
      (node (ref "IC11") (pin "7") (pinfunction "B_7") (pintype "passive"))
      (node (ref "IC11") (pin "8") (pinfunction "E_8") (pintype "passive"))
    )
    (net (code "68") (name "Net-(IC11B-B)") (class "Default")
      (node (ref "IC11") (pin "10") (pinfunction "B_10") (pintype "passive"))
      (node (ref "IC11") (pin "9") (pinfunction "E_9") (pintype "passive"))
    )
    (net (code "69") (name "Net-(IC11C-IN_N)") (class "Default")
      (node (ref "IC11") (pin "4") (pinfunction "IN_N_4") (pintype "input"))
      (node (ref "R11") (pin "1") (pinfunction "1_1") (pintype "passive"))
      (node (ref "R9") (pin "1") (pinfunction "1_1") (pintype "passive"))
    )
    (net (code "70") (name "Net-(IC11C-IN_P)") (class "Default")
      (node (ref "IC11") (pin "3") (pinfunction "IN_P_3") (pintype "input"))
      (node (ref "R10") (pin "1") (pinfunction "1_1") (pintype "passive"))
      (node (ref "R8") (pin "1") (pinfunction "1_1") (pintype "passive"))
    )
    (net (code "71") (name "Net-(IC11C-I_BIAS)") (class "Default")
      (node (ref "IC11") (pin "1") (pinfunction "I_BIAS_1") (pintype "input"))
      (node (ref "R7") (pin "1") (pinfunction "1_1") (pintype "passive"))
    )
    (net (code "72") (name "Net-(IC11C-OUT)") (class "Default")
      (node (ref "IC11") (pin "5") (pinfunction "OUT_5") (pintype "output"))
      (node (ref "IC5") (pin "13") (pinfunction "-IN_13") (pintype "input"))
      (node (ref "R12") (pin "2") (pinfunction "2_2") (pintype "passive"))
      (node (ref "TR1") (pin "1") (pinfunction "1_1") (pintype "passive"))
      (node (ref "TR1") (pin "2") (pinfunction "2_2") (pintype "passive"))
    )
    (net (code "73") (name "Net-(Q1-C)") (class "Default")
      (node (ref "Q1") (pin "1") (pinfunction "C_1") (pintype "passive"))
      (node (ref "R7") (pin "2") (pinfunction "2_2") (pintype "passive"))
    )
    (net (code "74") (name "Net-(Q1-E)") (class "Default")
      (node (ref "Q1") (pin "3") (pinfunction "E_3") (pintype "passive"))
      (node (ref "R5") (pin "1") (pinfunction "1_1") (pintype "passive"))
      (node (ref "R6") (pin "2") (pinfunction "2_2") (pintype "passive"))
    )
    (net (code "75") (name "Net-(Q2-PadE)") (class "Default")
      (node (ref "Q2") (pin "E") (pinfunction "E_E") (pintype "passive"))
      (node (ref "Q3") (pin "B") (pinfunction "B_B") (pintype "passive"))
      (node (ref "R14") (pin "1") (pinfunction "1_1") (pintype "passive"))
    )
    (net (code "76") (name "Net-(Q4-PadC)") (class "Default")
      (node (ref "Q4") (pin "C") (pinfunction "C_C") (pintype "passive"))
      (node (ref "Q5") (pin "B") (pinfunction "B_B") (pintype "passive"))
      (node (ref "R18") (pin "2") (pinfunction "2_2") (pintype "passive"))
    )
    (net (code "77") (name "Net-(Q4-PadE)") (class "Default")
      (node (ref "Q4") (pin "E") (pinfunction "E_E") (pintype "passive"))
      (node (ref "Q5") (pin "E") (pinfunction "E_E") (pintype "passive"))
      (node (ref "R19") (pin "1") (pinfunction "1_1") (pintype "passive"))
    )
    (net (code "78") (name "Net-(Q5-PadC)") (class "Default")
      (node (ref "Q5") (pin "C") (pinfunction "C_C") (pintype "passive"))
      (node (ref "R20") (pin "2") (pinfunction "2_2") (pintype "passive"))
      (node (ref "R21") (pin "1") (pinfunction "1_1") (pintype "passive"))
    )
    (net (code "79") (name "Net-(Q6-PadB)") (class "Default")
      (node (ref "Q6") (pin "B") (pinfunction "B_B") (pintype "passive"))
      (node (ref "R21") (pin "2") (pinfunction "2_2") (pintype "passive"))
    )
    (net (code "80") (name "Net-(R13-Pad2)") (class "Default")
      (node (ref "R13") (pin "2") (pinfunction "2_2") (pintype "passive"))
      (node (ref "TR2") (pin "E") (pinfunction "E_E") (pintype "passive"))
      (node (ref "TR2") (pin "S") (pinfunction "S_S") (pintype "passive"))
    )
    (net (code "81") (name "Net-(X2A-KL)") (class "Default")
      (node (ref "D2") (pin "C") (pinfunction "C_C") (pintype "passive"))
      (node (ref "X2") (pin "1") (pinfunction "KL_1") (pintype "passive"))
      (node (ref "X2") (pin "2") (pinfunction "KL_2") (pintype "passive"))
    )
    (net (code "82") (name "Net-(X2B-KL)") (class "Default")
      (node (ref "D1") (pin "A") (pinfunction "A_A") (pintype "passive"))
      (node (ref "X2") (pin "10") (pinfunction "KL_10") (pintype "passive"))
      (node (ref "X2") (pin "9") (pinfunction "KL_9") (pintype "passive"))
    )
    (net (code "83") (name "unconnected-(IC1B-O-Pad4)") (class "Default")
      (node (ref "IC1") (pin "4") (pinfunction "O_4") (pintype "output"))
    )
    (net (code "84") (name "unconnected-(IC1C-O-Pad6)") (class "Default")
      (node (ref "IC1") (pin "6") (pinfunction "O_6") (pintype "output"))
    )
    (net (code "85") (name "unconnected-(IC1D-O-Pad8)") (class "Default")
      (node (ref "IC1") (pin "8") (pinfunction "O_8") (pintype "output"))
    )
    (net (code "86") (name "unconnected-(IC1E-O-Pad10)") (class "Default")
      (node (ref "IC1") (pin "10") (pinfunction "O_10") (pintype "output"))
    )
    (net (code "87") (name "unconnected-(IC1F-O-Pad12)") (class "Default")
      (node (ref "IC1") (pin "12") (pinfunction "O_12") (pintype "output"))
    )
    (net (code "88") (name "unconnected-(IC4-COUT{slash}T0CKI{slash}INT{slash}AN2{slash}RA2-Pad11)") (class "Default")
      (node (ref "IC4") (pin "11") (pinfunction "COUT/T0CKI/INT/AN2/RA2_11") (pintype "bidirectional"))
    )
    (net (code "89") (name "unconnected-(IC7A-CO-Pad12)") (class "Default")
      (node (ref "IC7") (pin "12") (pinfunction "CO_12") (pintype "output"))
    )
    (net (code "90") (name "unconnected-(IC7A-Q1-Pad2)") (class "Default")
      (node (ref "IC7") (pin "2") (pinfunction "Q1_2") (pintype "output"))
    )
    (net (code "91") (name "unconnected-(IC8A-CO-Pad12)") (class "Default")
      (node (ref "IC8") (pin "12") (pinfunction "CO_12") (pintype "output"))
    )
    (net (code "92") (name "unconnected-(IC8A-Q9-Pad11)") (class "Default")
      (node (ref "IC8") (pin "11") (pinfunction "Q9_11") (pintype "output"))
    )
    (net (code "93") (name "unconnected-(IC11C-I_DIODE-Pad2)") (class "Default")
      (node (ref "IC11") (pin "2") (pinfunction "I_DIODE_2") (pintype "input"))
    )
    (net (code "94") (name "unconnected-(IC11D-I_DIODE-Pad15)") (class "Default")
      (node (ref "IC11") (pin "15") (pinfunction "I_DIODE_15") (pintype "input"))
    )
    (net (code "95") (name "unconnected-(IC11D-OUT-Pad12)") (class "Default")
      (node (ref "IC11") (pin "12") (pinfunction "OUT_12") (pintype "output"))
    )
    (net (code "96") (name "unconnected-(JP1-Pad6)") (class "Default")
      (node (ref "JP1") (pin "6") (pinfunction "6_6") (pintype "passive"))
    )
    (net (code "97") (name "unconnected-(JP2-Pad5)") (class "Default")
      (node (ref "JP2") (pin "5") (pinfunction "5_5") (pintype "passive"))
    )
    (net (code "98") (name "unconnected-(JP2-Pad8)") (class "Default")
      (node (ref "JP2") (pin "8") (pinfunction "8_8") (pintype "passive"))
    )
    (net (code "99") (name "unconnected-(JP2-Pad10)") (class "Default")
      (node (ref "JP2") (pin "10") (pinfunction "10_10") (pintype "passive"))
    )
    (net (code "100") (name "unconnected-(JP2-Pad11)") (class "Default")
      (node (ref "JP2") (pin "11") (pinfunction "11_11") (pintype "passive"))
    )
    (net (code "101") (name "unconnected-(JP2-Pad12)") (class "Default")
      (node (ref "JP2") (pin "12") (pinfunction "12_12") (pintype "passive"))
    )
    (net (code "102") (name "unconnected-(JP2-Pad13)") (class "Default")
      (node (ref "JP2") (pin "13") (pinfunction "13_13") (pintype "passive"))
    )
    (net (code "103") (name "unconnected-(JP2-Pad14)") (class "Default")
      (node (ref "JP2") (pin "14") (pinfunction "14_14") (pintype "passive"))
    )
    (net (code "104") (name "unconnected-(JP2-Pad16)") (class "Default")
      (node (ref "JP2") (pin "16") (pinfunction "16_16") (pintype "passive"))
    )
    (net (code "105") (name "unconnected-(JP2-Pad17)") (class "Default")
      (node (ref "JP2") (pin "17") (pinfunction "17_17") (pintype "passive"))
    )
    (net (code "106") (name "unconnected-(JP2-Pad18)") (class "Default")
      (node (ref "JP2") (pin "18") (pinfunction "18_18") (pintype "passive"))
    )
    (net (code "107") (name "unconnected-(JP3-Pad3)") (class "Default")
      (node (ref "JP3") (pin "3") (pinfunction "3_3") (pintype "passive"))
    )
    (net (code "108") (name "unconnected-(JP3-Pad4)") (class "Default")
      (node (ref "JP3") (pin "4") (pinfunction "4_4") (pintype "passive"))
    )
    (net (code "109") (name "unconnected-(JP3-Pad6)") (class "Default")
      (node (ref "JP3") (pin "6") (pinfunction "6_6") (pintype "passive"))
    )
    (net (code "110") (name "unconnected-(JP3-Pad15)") (class "Default")
      (node (ref "JP3") (pin "15") (pinfunction "15_15") (pintype "passive"))
    )
    (net (code "111") (name "unconnected-(JP3-Pad19)") (class "Default")
      (node (ref "JP3") (pin "19") (pinfunction "19_19") (pintype "passive"))
    )
  )
)
